# NixieConnector.net
KiCad netlist of a schematic drawn in EAGLE
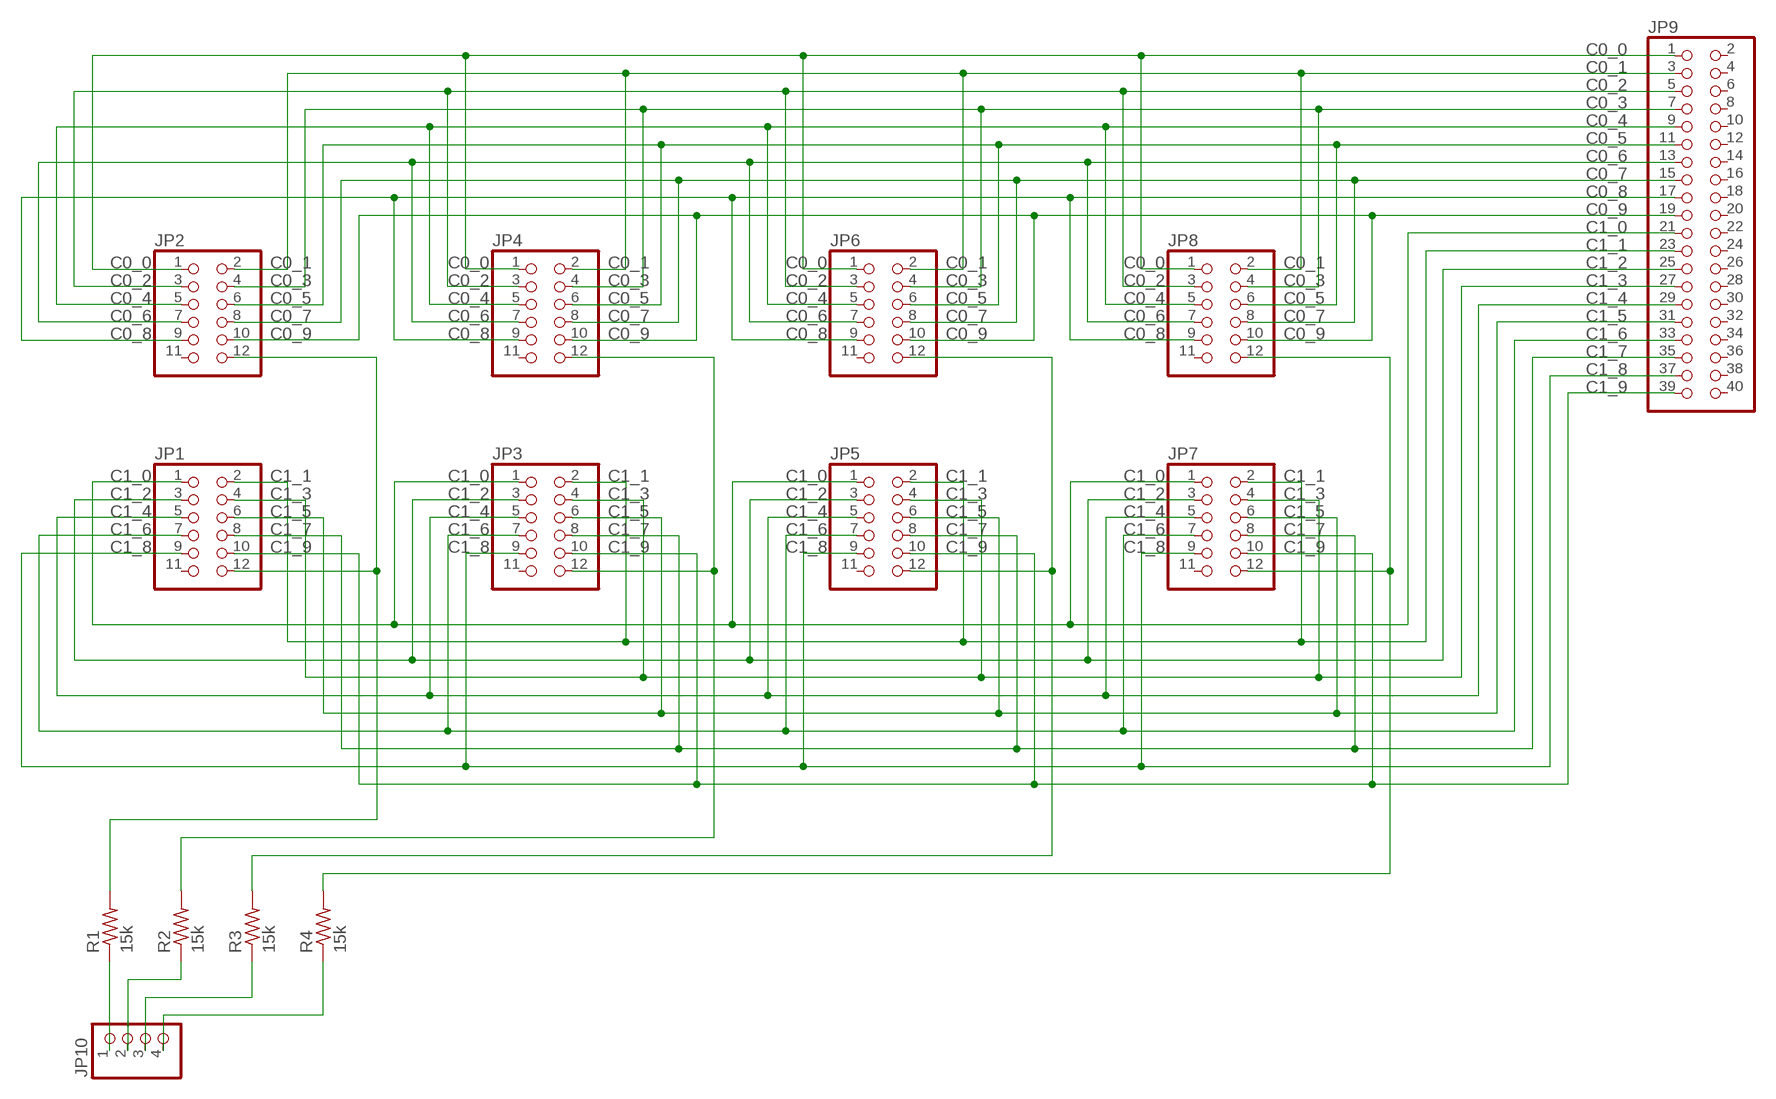
[diagram p0: schematic, sheet 1]

(export (version "E")
  (design (tool "Eeschema 10.0.6"))
  (components
    (comp (ref "JP1")
      (value "PINHD-2X6")
      (footprint "eagle-import:2X06")
      (libsource (lib "eagle-import") (part "PINHD-2X6"))
    )
    (comp (ref "JP2")
      (value "PINHD-2X6")
      (footprint "eagle-import:2X06")
      (libsource (lib "eagle-import") (part "PINHD-2X6"))
    )
    (comp (ref "JP3")
      (value "PINHD-2X6")
      (footprint "eagle-import:2X06")
      (libsource (lib "eagle-import") (part "PINHD-2X6"))
    )
    (comp (ref "JP4")
      (value "PINHD-2X6")
      (footprint "eagle-import:2X06")
      (libsource (lib "eagle-import") (part "PINHD-2X6"))
    )
    (comp (ref "JP5")
      (value "PINHD-2X6")
      (footprint "eagle-import:2X06")
      (libsource (lib "eagle-import") (part "PINHD-2X6"))
    )
    (comp (ref "JP6")
      (value "PINHD-2X6")
      (footprint "eagle-import:2X06")
      (libsource (lib "eagle-import") (part "PINHD-2X6"))
    )
    (comp (ref "JP7")
      (value "PINHD-2X6")
      (footprint "eagle-import:2X06")
      (libsource (lib "eagle-import") (part "PINHD-2X6"))
    )
    (comp (ref "JP8")
      (value "PINHD-2X6")
      (footprint "eagle-import:2X06")
      (libsource (lib "eagle-import") (part "PINHD-2X6"))
    )
    (comp (ref "JP9")
      (value "PINHD-2X20")
      (footprint "eagle-import:2X20")
      (libsource (lib "eagle-import") (part "PINHD-2X20"))
    )
    (comp (ref "JP10")
      (value "PINHD-1X4")
      (footprint "eagle-import:1X04")
      (libsource (lib "eagle-import") (part "PINHD-1X4"))
    )
    (comp (ref "R1")
      (value "15k")
      (footprint "eagle-import:0204_5")
      (libsource (lib "eagle-import") (part "R-US_0204/5"))
    )
    (comp (ref "R2")
      (value "15k")
      (footprint "eagle-import:0204_5")
      (libsource (lib "eagle-import") (part "R-US_0204/5"))
    )
    (comp (ref "R3")
      (value "15k")
      (footprint "eagle-import:0204_5")
      (libsource (lib "eagle-import") (part "R-US_0204/5"))
    )
    (comp (ref "R4")
      (value "15k")
      (footprint "eagle-import:0204_5")
      (libsource (lib "eagle-import") (part "R-US_0204/5"))
    )
  )
  (nets
    (net (code "1") (name "/C0_0") (class "Default")
      (node (ref "JP2") (pin "1") (pinfunction "1_1") (pintype "passive"))
      (node (ref "JP4") (pin "1") (pinfunction "1_1") (pintype "passive"))
      (node (ref "JP6") (pin "1") (pinfunction "1_1") (pintype "passive"))
      (node (ref "JP8") (pin "1") (pinfunction "1_1") (pintype "passive"))
      (node (ref "JP9") (pin "1") (pinfunction "1_1") (pintype "passive"))
    )
    (net (code "2") (name "/C0_1") (class "Default")
      (node (ref "JP2") (pin "2") (pinfunction "2_2") (pintype "passive"))
      (node (ref "JP4") (pin "2") (pinfunction "2_2") (pintype "passive"))
      (node (ref "JP6") (pin "2") (pinfunction "2_2") (pintype "passive"))
      (node (ref "JP8") (pin "2") (pinfunction "2_2") (pintype "passive"))
      (node (ref "JP9") (pin "3") (pinfunction "3_3") (pintype "passive"))
    )
    (net (code "3") (name "/C0_2") (class "Default")
      (node (ref "JP2") (pin "3") (pinfunction "3_3") (pintype "passive"))
      (node (ref "JP4") (pin "3") (pinfunction "3_3") (pintype "passive"))
      (node (ref "JP6") (pin "3") (pinfunction "3_3") (pintype "passive"))
      (node (ref "JP8") (pin "3") (pinfunction "3_3") (pintype "passive"))
      (node (ref "JP9") (pin "5") (pinfunction "5_5") (pintype "passive"))
    )
    (net (code "4") (name "/C0_3") (class "Default")
      (node (ref "JP2") (pin "4") (pinfunction "4_4") (pintype "passive"))
      (node (ref "JP4") (pin "4") (pinfunction "4_4") (pintype "passive"))
      (node (ref "JP6") (pin "4") (pinfunction "4_4") (pintype "passive"))
      (node (ref "JP8") (pin "4") (pinfunction "4_4") (pintype "passive"))
      (node (ref "JP9") (pin "7") (pinfunction "7_7") (pintype "passive"))
    )
    (net (code "5") (name "/C0_4") (class "Default")
      (node (ref "JP2") (pin "5") (pinfunction "5_5") (pintype "passive"))
      (node (ref "JP4") (pin "5") (pinfunction "5_5") (pintype "passive"))
      (node (ref "JP6") (pin "5") (pinfunction "5_5") (pintype "passive"))
      (node (ref "JP8") (pin "5") (pinfunction "5_5") (pintype "passive"))
      (node (ref "JP9") (pin "9") (pinfunction "9_9") (pintype "passive"))
    )
    (net (code "6") (name "/C0_5") (class "Default")
      (node (ref "JP2") (pin "6") (pinfunction "6_6") (pintype "passive"))
      (node (ref "JP4") (pin "6") (pinfunction "6_6") (pintype "passive"))
      (node (ref "JP6") (pin "6") (pinfunction "6_6") (pintype "passive"))
      (node (ref "JP8") (pin "6") (pinfunction "6_6") (pintype "passive"))
      (node (ref "JP9") (pin "11") (pinfunction "11_11") (pintype "passive"))
    )
    (net (code "7") (name "/C0_6") (class "Default")
      (node (ref "JP2") (pin "7") (pinfunction "7_7") (pintype "passive"))
      (node (ref "JP4") (pin "7") (pinfunction "7_7") (pintype "passive"))
      (node (ref "JP6") (pin "7") (pinfunction "7_7") (pintype "passive"))
      (node (ref "JP8") (pin "7") (pinfunction "7_7") (pintype "passive"))
      (node (ref "JP9") (pin "13") (pinfunction "13_13") (pintype "passive"))
    )
    (net (code "8") (name "/C0_7") (class "Default")
      (node (ref "JP2") (pin "8") (pinfunction "8_8") (pintype "passive"))
      (node (ref "JP4") (pin "8") (pinfunction "8_8") (pintype "passive"))
      (node (ref "JP6") (pin "8") (pinfunction "8_8") (pintype "passive"))
      (node (ref "JP8") (pin "8") (pinfunction "8_8") (pintype "passive"))
      (node (ref "JP9") (pin "15") (pinfunction "15_15") (pintype "passive"))
    )
    (net (code "9") (name "/C0_8") (class "Default")
      (node (ref "JP2") (pin "9") (pinfunction "9_9") (pintype "passive"))
      (node (ref "JP4") (pin "9") (pinfunction "9_9") (pintype "passive"))
      (node (ref "JP6") (pin "9") (pinfunction "9_9") (pintype "passive"))
      (node (ref "JP8") (pin "9") (pinfunction "9_9") (pintype "passive"))
      (node (ref "JP9") (pin "17") (pinfunction "17_17") (pintype "passive"))
    )
    (net (code "10") (name "/C0_9") (class "Default")
      (node (ref "JP2") (pin "10") (pinfunction "10_10") (pintype "passive"))
      (node (ref "JP4") (pin "10") (pinfunction "10_10") (pintype "passive"))
      (node (ref "JP6") (pin "10") (pinfunction "10_10") (pintype "passive"))
      (node (ref "JP8") (pin "10") (pinfunction "10_10") (pintype "passive"))
      (node (ref "JP9") (pin "19") (pinfunction "19_19") (pintype "passive"))
    )
    (net (code "11") (name "/C1_0") (class "Default")
      (node (ref "JP1") (pin "1") (pinfunction "1_1") (pintype "passive"))
      (node (ref "JP3") (pin "1") (pinfunction "1_1") (pintype "passive"))
      (node (ref "JP5") (pin "1") (pinfunction "1_1") (pintype "passive"))
      (node (ref "JP7") (pin "1") (pinfunction "1_1") (pintype "passive"))
      (node (ref "JP9") (pin "21") (pinfunction "21_21") (pintype "passive"))
    )
    (net (code "12") (name "/C1_1") (class "Default")
      (node (ref "JP1") (pin "2") (pinfunction "2_2") (pintype "passive"))
      (node (ref "JP3") (pin "2") (pinfunction "2_2") (pintype "passive"))
      (node (ref "JP5") (pin "2") (pinfunction "2_2") (pintype "passive"))
      (node (ref "JP7") (pin "2") (pinfunction "2_2") (pintype "passive"))
      (node (ref "JP9") (pin "23") (pinfunction "23_23") (pintype "passive"))
    )
    (net (code "13") (name "/C1_2") (class "Default")
      (node (ref "JP1") (pin "3") (pinfunction "3_3") (pintype "passive"))
      (node (ref "JP3") (pin "3") (pinfunction "3_3") (pintype "passive"))
      (node (ref "JP5") (pin "3") (pinfunction "3_3") (pintype "passive"))
      (node (ref "JP7") (pin "3") (pinfunction "3_3") (pintype "passive"))
      (node (ref "JP9") (pin "25") (pinfunction "25_25") (pintype "passive"))
    )
    (net (code "14") (name "/C1_3") (class "Default")
      (node (ref "JP1") (pin "4") (pinfunction "4_4") (pintype "passive"))
      (node (ref "JP3") (pin "4") (pinfunction "4_4") (pintype "passive"))
      (node (ref "JP5") (pin "4") (pinfunction "4_4") (pintype "passive"))
      (node (ref "JP7") (pin "4") (pinfunction "4_4") (pintype "passive"))
      (node (ref "JP9") (pin "27") (pinfunction "27_27") (pintype "passive"))
    )
    (net (code "15") (name "/C1_4") (class "Default")
      (node (ref "JP1") (pin "5") (pinfunction "5_5") (pintype "passive"))
      (node (ref "JP3") (pin "5") (pinfunction "5_5") (pintype "passive"))
      (node (ref "JP5") (pin "5") (pinfunction "5_5") (pintype "passive"))
      (node (ref "JP7") (pin "5") (pinfunction "5_5") (pintype "passive"))
      (node (ref "JP9") (pin "29") (pinfunction "29_29") (pintype "passive"))
    )
    (net (code "16") (name "/C1_5") (class "Default")
      (node (ref "JP1") (pin "6") (pinfunction "6_6") (pintype "passive"))
      (node (ref "JP3") (pin "6") (pinfunction "6_6") (pintype "passive"))
      (node (ref "JP5") (pin "6") (pinfunction "6_6") (pintype "passive"))
      (node (ref "JP7") (pin "6") (pinfunction "6_6") (pintype "passive"))
      (node (ref "JP9") (pin "31") (pinfunction "31_31") (pintype "passive"))
    )
    (net (code "17") (name "/C1_6") (class "Default")
      (node (ref "JP1") (pin "7") (pinfunction "7_7") (pintype "passive"))
      (node (ref "JP3") (pin "7") (pinfunction "7_7") (pintype "passive"))
      (node (ref "JP5") (pin "7") (pinfunction "7_7") (pintype "passive"))
      (node (ref "JP7") (pin "7") (pinfunction "7_7") (pintype "passive"))
      (node (ref "JP9") (pin "33") (pinfunction "33_33") (pintype "passive"))
    )
    (net (code "18") (name "/C1_7") (class "Default")
      (node (ref "JP1") (pin "8") (pinfunction "8_8") (pintype "passive"))
      (node (ref "JP3") (pin "8") (pinfunction "8_8") (pintype "passive"))
      (node (ref "JP5") (pin "8") (pinfunction "8_8") (pintype "passive"))
      (node (ref "JP7") (pin "8") (pinfunction "8_8") (pintype "passive"))
      (node (ref "JP9") (pin "35") (pinfunction "35_35") (pintype "passive"))
    )
    (net (code "19") (name "/C1_8") (class "Default")
      (node (ref "JP1") (pin "9") (pinfunction "9_9") (pintype "passive"))
      (node (ref "JP3") (pin "9") (pinfunction "9_9") (pintype "passive"))
      (node (ref "JP5") (pin "9") (pinfunction "9_9") (pintype "passive"))
      (node (ref "JP7") (pin "9") (pinfunction "9_9") (pintype "passive"))
      (node (ref "JP9") (pin "37") (pinfunction "37_37") (pintype "passive"))
    )
    (net (code "20") (name "/C1_9") (class "Default")
      (node (ref "JP1") (pin "10") (pinfunction "10_10") (pintype "passive"))
      (node (ref "JP3") (pin "10") (pinfunction "10_10") (pintype "passive"))
      (node (ref "JP5") (pin "10") (pinfunction "10_10") (pintype "passive"))
      (node (ref "JP7") (pin "10") (pinfunction "10_10") (pintype "passive"))
      (node (ref "JP9") (pin "39") (pinfunction "39_39") (pintype "passive"))
    )
    (net (code "21") (name "Net-(JP1-Pad12)") (class "Default")
      (node (ref "JP1") (pin "12") (pinfunction "12_12") (pintype "passive"))
      (node (ref "JP2") (pin "12") (pinfunction "12_12") (pintype "passive"))
      (node (ref "R1") (pin "2") (pinfunction "2_2") (pintype "passive"))
    )
    (net (code "22") (name "Net-(JP3-Pad12)") (class "Default")
      (node (ref "JP3") (pin "12") (pinfunction "12_12") (pintype "passive"))
      (node (ref "JP4") (pin "12") (pinfunction "12_12") (pintype "passive"))
      (node (ref "R2") (pin "2") (pinfunction "2_2") (pintype "passive"))
    )
    (net (code "23") (name "Net-(JP5-Pad12)") (class "Default")
      (node (ref "JP5") (pin "12") (pinfunction "12_12") (pintype "passive"))
      (node (ref "JP6") (pin "12") (pinfunction "12_12") (pintype "passive"))
      (node (ref "R3") (pin "2") (pinfunction "2_2") (pintype "passive"))
    )
    (net (code "24") (name "Net-(JP7-Pad12)") (class "Default")
      (node (ref "JP7") (pin "12") (pinfunction "12_12") (pintype "passive"))
      (node (ref "JP8") (pin "12") (pinfunction "12_12") (pintype "passive"))
      (node (ref "R4") (pin "2") (pinfunction "2_2") (pintype "passive"))
    )
    (net (code "25") (name "Net-(JP10-Pad1)") (class "Default")
      (node (ref "JP10") (pin "1") (pinfunction "1_1") (pintype "passive"))
      (node (ref "R1") (pin "1") (pinfunction "1_1") (pintype "passive"))
    )
    (net (code "26") (name "Net-(JP10-Pad2)") (class "Default")
      (node (ref "JP10") (pin "2") (pinfunction "2_2") (pintype "passive"))
      (node (ref "R2") (pin "1") (pinfunction "1_1") (pintype "passive"))
    )
    (net (code "27") (name "Net-(JP10-Pad3)") (class "Default")
      (node (ref "JP10") (pin "3") (pinfunction "3_3") (pintype "passive"))
      (node (ref "R3") (pin "1") (pinfunction "1_1") (pintype "passive"))
    )
    (net (code "28") (name "Net-(JP10-Pad4)") (class "Default")
      (node (ref "JP10") (pin "4") (pinfunction "4_4") (pintype "passive"))
      (node (ref "R4") (pin "1") (pinfunction "1_1") (pintype "passive"))
    )
    (net (code "29") (name "unconnected-(JP1-Pad11)") (class "Default")
      (node (ref "JP1") (pin "11") (pinfunction "11_11") (pintype "passive"))
    )
    (net (code "30") (name "unconnected-(JP2-Pad11)") (class "Default")
      (node (ref "JP2") (pin "11") (pinfunction "11_11") (pintype "passive"))
    )
    (net (code "31") (name "unconnected-(JP3-Pad11)") (class "Default")
      (node (ref "JP3") (pin "11") (pinfunction "11_11") (pintype "passive"))
    )
    (net (code "32") (name "unconnected-(JP4-Pad11)") (class "Default")
      (node (ref "JP4") (pin "11") (pinfunction "11_11") (pintype "passive"))
    )
    (net (code "33") (name "unconnected-(JP5-Pad11)") (class "Default")
      (node (ref "JP5") (pin "11") (pinfunction "11_11") (pintype "passive"))
    )
    (net (code "34") (name "unconnected-(JP6-Pad11)") (class "Default")
      (node (ref "JP6") (pin "11") (pinfunction "11_11") (pintype "passive"))
    )
    (net (code "35") (name "unconnected-(JP7-Pad11)") (class "Default")
      (node (ref "JP7") (pin "11") (pinfunction "11_11") (pintype "passive"))
    )
    (net (code "36") (name "unconnected-(JP8-Pad11)") (class "Default")
      (node (ref "JP8") (pin "11") (pinfunction "11_11") (pintype "passive"))
    )
    (net (code "37") (name "unconnected-(JP9-Pad2)") (class "Default")
      (node (ref "JP9") (pin "2") (pinfunction "2_2") (pintype "passive"))
    )
    (net (code "38") (name "unconnected-(JP9-Pad4)") (class "Default")
      (node (ref "JP9") (pin "4") (pinfunction "4_4") (pintype "passive"))
    )
    (net (code "39") (name "unconnected-(JP9-Pad6)") (class "Default")
      (node (ref "JP9") (pin "6") (pinfunction "6_6") (pintype "passive"))
    )
    (net (code "40") (name "unconnected-(JP9-Pad8)") (class "Default")
      (node (ref "JP9") (pin "8") (pinfunction "8_8") (pintype "passive"))
    )
    (net (code "41") (name "unconnected-(JP9-Pad10)") (class "Default")
      (node (ref "JP9") (pin "10") (pinfunction "10_10") (pintype "passive"))
    )
    (net (code "42") (name "unconnected-(JP9-Pad12)") (class "Default")
      (node (ref "JP9") (pin "12") (pinfunction "12_12") (pintype "passive"))
    )
    (net (code "43") (name "unconnected-(JP9-Pad14)") (class "Default")
      (node (ref "JP9") (pin "14") (pinfunction "14_14") (pintype "passive"))
    )
    (net (code "44") (name "unconnected-(JP9-Pad16)") (class "Default")
      (node (ref "JP9") (pin "16") (pinfunction "16_16") (pintype "passive"))
    )
    (net (code "45") (name "unconnected-(JP9-Pad18)") (class "Default")
      (node (ref "JP9") (pin "18") (pinfunction "18_18") (pintype "passive"))
    )
    (net (code "46") (name "unconnected-(JP9-Pad20)") (class "Default")
      (node (ref "JP9") (pin "20") (pinfunction "20_20") (pintype "passive"))
    )
    (net (code "47") (name "unconnected-(JP9-Pad22)") (class "Default")
      (node (ref "JP9") (pin "22") (pinfunction "22_22") (pintype "passive"))
    )
    (net (code "48") (name "unconnected-(JP9-Pad24)") (class "Default")
      (node (ref "JP9") (pin "24") (pinfunction "24_24") (pintype "passive"))
    )
    (net (code "49") (name "unconnected-(JP9-Pad26)") (class "Default")
      (node (ref "JP9") (pin "26") (pinfunction "26_26") (pintype "passive"))
    )
    (net (code "50") (name "unconnected-(JP9-Pad28)") (class "Default")
      (node (ref "JP9") (pin "28") (pinfunction "28_28") (pintype "passive"))
    )
    (net (code "51") (name "unconnected-(JP9-Pad30)") (class "Default")
      (node (ref "JP9") (pin "30") (pinfunction "30_30") (pintype "passive"))
    )
    (net (code "52") (name "unconnected-(JP9-Pad32)") (class "Default")
      (node (ref "JP9") (pin "32") (pinfunction "32_32") (pintype "passive"))
    )
    (net (code "53") (name "unconnected-(JP9-Pad34)") (class "Default")
      (node (ref "JP9") (pin "34") (pinfunction "34_34") (pintype "passive"))
    )
    (net (code "54") (name "unconnected-(JP9-Pad36)") (class "Default")
      (node (ref "JP9") (pin "36") (pinfunction "36_36") (pintype "passive"))
    )
    (net (code "55") (name "unconnected-(JP9-Pad38)") (class "Default")
      (node (ref "JP9") (pin "38") (pinfunction "38_38") (pintype "passive"))
    )
    (net (code "56") (name "unconnected-(JP9-Pad40)") (class "Default")
      (node (ref "JP9") (pin "40") (pinfunction "40_40") (pintype "passive"))
    )
  )
)
